# Sheet1.net
KiCad netlist of a schematic drawn in Altium Designer
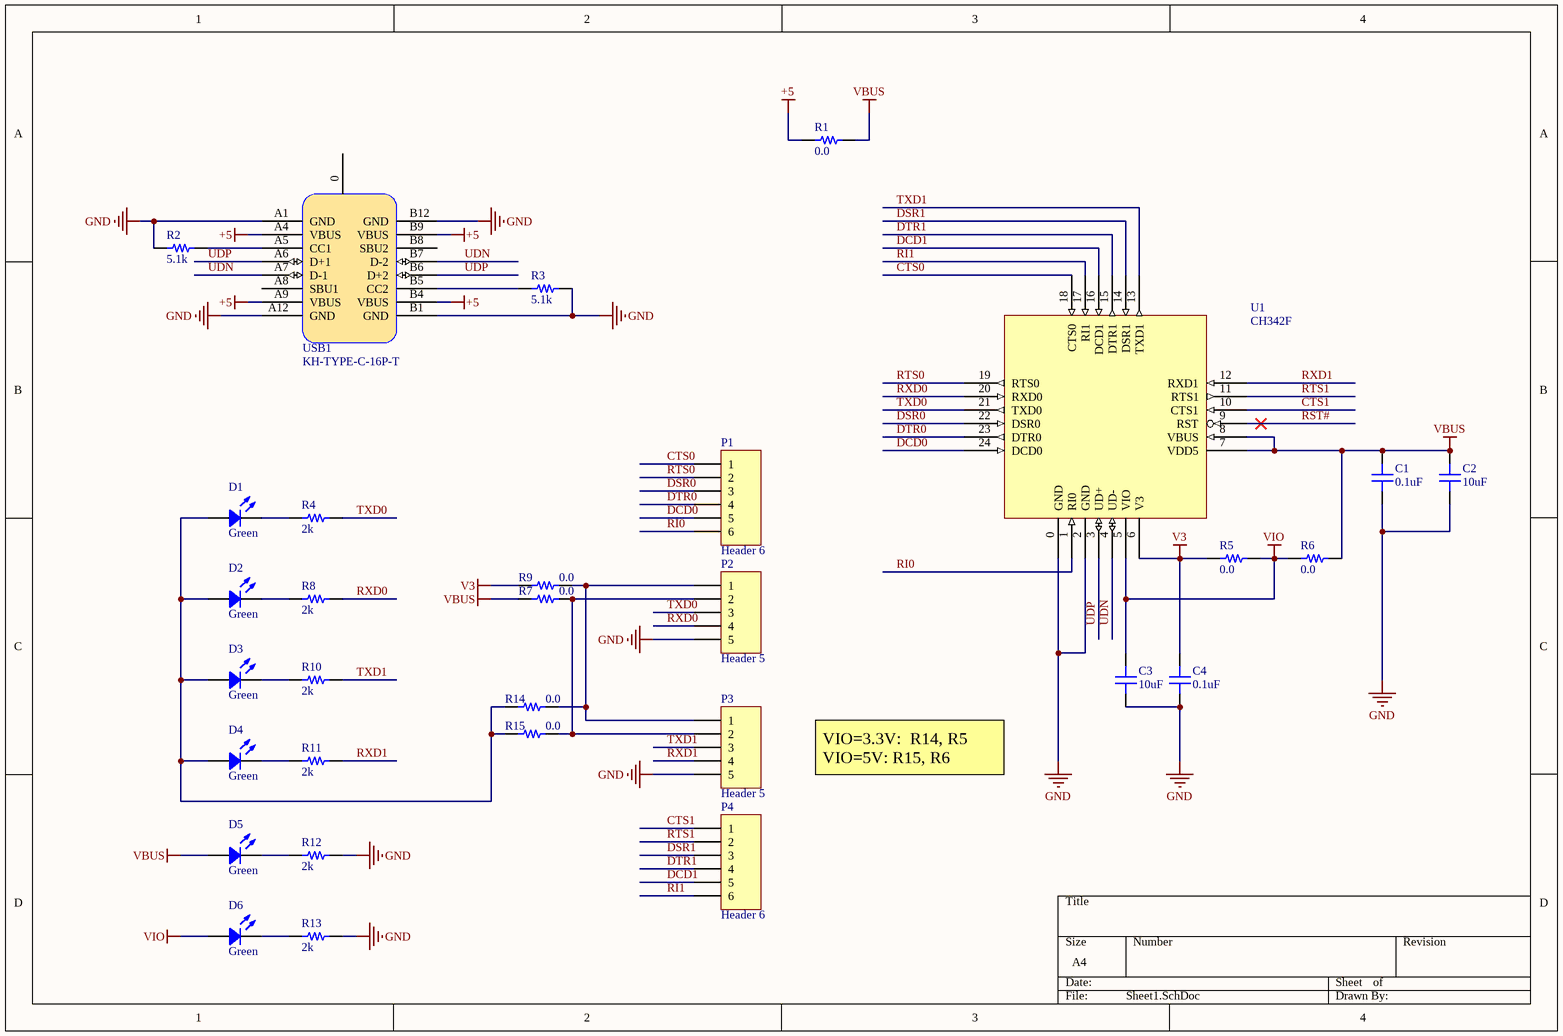
[diagram p0: Sheet1.SchDoc]

(export (version "E")
  (design (tool "Eeschema 10.0.6"))
  (components
    (comp (ref "C1")
      (value "0.1uF")
      (footprint "CAP 0402/1005")
      (description "CAP CER 0.1UF 16V X7R 0402")
      (fields
        (field (name "PART NUMBER") "C1005X7R1C104K050BC")
        (field (name "MANUFACTURER") "TDK Corporation")
      )
      (libsource (lib "Celestial Library Database") (part "Capacitor"))
    )
    (comp (ref "C2")
      (value "10uF")
      (footprint "CAP 0805/2012")
      (description "CAP CER 10UF 10V X5R 0805")
      (fields
        (field (name "PART NUMBER") "C2012X5R1A106K125AB")
        (field (name "MANUFACTURER") "TDK Corporation")
      )
      (libsource (lib "Celestial Library Database") (part "Capacitor"))
    )
    (comp (ref "C3")
      (value "10uF")
      (footprint "CAP 0805/2012")
      (description "CAP CER 10UF 10V X5R 0805")
      (fields
        (field (name "PART NUMBER") "C2012X5R1A106K125AB")
        (field (name "MANUFACTURER") "TDK Corporation")
      )
      (libsource (lib "Celestial Library Database") (part "Capacitor"))
    )
    (comp (ref "C4")
      (value "0.1uF")
      (footprint "CAP 0402/1005")
      (description "CAP CER 0.1UF 16V X7R 0402")
      (fields
        (field (name "PART NUMBER") "C1005X7R1C104K050BC")
        (field (name "MANUFACTURER") "TDK Corporation")
      )
      (libsource (lib "Celestial Library Database") (part "Capacitor"))
    )
    (comp (ref "D1")
      (value "Green")
      (footprint "LED 0805/2012 GREEN")
      (description "LED GREEN CLEAR 0805 SMD")
      (fields (field (name "PART NUMBER") "LTST-C171GKT") (field (name "MANUFACTURER") "Lite-On Inc."))
      (libsource (lib "Celestial Library Database") (part "LED"))
    )
    (comp (ref "D2")
      (value "Green")
      (footprint "LED 0805/2012 GREEN")
      (description "LED GREEN CLEAR 0805 SMD")
      (fields (field (name "PART NUMBER") "LTST-C171GKT") (field (name "MANUFACTURER") "Lite-On Inc."))
      (libsource (lib "Celestial Library Database") (part "LED"))
    )
    (comp (ref "D3")
      (value "Green")
      (footprint "LED 0805/2012 GREEN")
      (description "LED GREEN CLEAR 0805 SMD")
      (fields (field (name "PART NUMBER") "LTST-C171GKT") (field (name "MANUFACTURER") "Lite-On Inc."))
      (libsource (lib "Celestial Library Database") (part "LED"))
    )
    (comp (ref "D4")
      (value "Green")
      (footprint "LED 0805/2012 GREEN")
      (description "LED GREEN CLEAR 0805 SMD")
      (fields (field (name "PART NUMBER") "LTST-C171GKT") (field (name "MANUFACTURER") "Lite-On Inc."))
      (libsource (lib "Celestial Library Database") (part "LED"))
    )
    (comp (ref "D5")
      (value "Green")
      (footprint "LED 0805/2012 GREEN")
      (description "LED GREEN CLEAR 0805 SMD")
      (fields (field (name "PART NUMBER") "LTST-C171GKT") (field (name "MANUFACTURER") "Lite-On Inc."))
      (libsource (lib "Celestial Library Database") (part "LED"))
    )
    (comp (ref "D6")
      (value "Green")
      (footprint "LED 0805/2012 GREEN")
      (description "LED GREEN CLEAR 0805 SMD")
      (fields (field (name "PART NUMBER") "LTST-C171GKT") (field (name "MANUFACTURER") "Lite-On Inc."))
      (libsource (lib "Celestial Library Database") (part "LED"))
    )
    (comp (ref "P1")
      (value "Header 6")
      (footprint "HDR1X6")
      (description "Header, 6-Pin")
      (fields (field (name "PUBLISHER") "Altium Limited"))
      (libsource (lib "Miscellaneous Connectors") (part "Header 6"))
    )
    (comp (ref "P2")
      (value "Header 5")
      (footprint "HDR1X5")
      (description "Header, 5-Pin")
      (fields (field (name "PUBLISHER") "Altium Limited"))
      (libsource (lib "Miscellaneous Connectors") (part "Header 5"))
    )
    (comp (ref "P3")
      (value "Header 5")
      (footprint "HDR1X5")
      (description "Header, 5-Pin")
      (fields (field (name "PUBLISHER") "Altium Limited"))
      (libsource (lib "Miscellaneous Connectors") (part "Header 5"))
    )
    (comp (ref "P4")
      (value "Header 6")
      (footprint "HDR1X6")
      (description "Header, 6-Pin")
      (fields (field (name "PUBLISHER") "Altium Limited"))
      (libsource (lib "Miscellaneous Connectors") (part "Header 6"))
    )
    (comp (ref "R1")
      (value "0.0")
      (footprint "RES 0805/2012")
      (description "RES SMD 0.0 OHM JUMPER 1/8W 0805")
      (fields (field (name "PART NUMBER") "MCR10EZPJ000") (field (name "MANUFACTURER") "Rohm Semiconductor"))
      (libsource (lib "Celestial Library Database") (part "Resistor"))
    )
    (comp (ref "R2")
      (value "5.1k")
      (footprint "RES 0402/1005")
      (description "RES SMD 5.1K OHM 1% 1/10W 0402")
      (fields
        (field (name "PART NUMBER") "ERJ-2RKF5101X")
        (field (name "MANUFACTURER") "Panasonic Electronic Components")
      )
      (libsource (lib "Celestial Library Database") (part "Resistor"))
    )
    (comp (ref "R3")
      (value "5.1k")
      (footprint "RES 0402/1005")
      (description "RES SMD 5.1K OHM 1% 1/10W 0402")
      (fields
        (field (name "PART NUMBER") "ERJ-2RKF5101X")
        (field (name "MANUFACTURER") "Panasonic Electronic Components")
      )
      (libsource (lib "Celestial Library Database") (part "Resistor"))
    )
    (comp (ref "R4")
      (value "2k")
      (footprint "RES 0402/1005")
      (description "RES SMD 2K OHM 5% 1/16W 0402")
      (fields (field (name "PART NUMBER") "RC0402JR-072KL") (field (name "MANUFACTURER") "Yageo"))
      (libsource (lib "Celestial Library Database") (part "Resistor"))
    )
    (comp (ref "R5")
      (value "0.0")
      (footprint "RES 0805/2012")
      (description "RES SMD 0.0 OHM JUMPER 1/8W 0805")
      (fields (field (name "PART NUMBER") "MCR10EZPJ000") (field (name "MANUFACTURER") "Rohm Semiconductor"))
      (libsource (lib "Celestial Library Database") (part "Resistor"))
    )
    (comp (ref "R6")
      (value "0.0")
      (footprint "RES 0805/2012")
      (description "RES SMD 0.0 OHM JUMPER 1/8W 0805")
      (fields (field (name "PART NUMBER") "MCR10EZPJ000") (field (name "MANUFACTURER") "Rohm Semiconductor"))
      (libsource (lib "Celestial Library Database") (part "Resistor"))
    )
    (comp (ref "R7")
      (value "0.0")
      (footprint "RES 0805/2012")
      (description "RES SMD 0.0 OHM JUMPER 1/8W 0805")
      (fields (field (name "PART NUMBER") "MCR10EZPJ000") (field (name "MANUFACTURER") "Rohm Semiconductor"))
      (libsource (lib "Celestial Library Database") (part "Resistor"))
    )
    (comp (ref "R8")
      (value "2k")
      (footprint "RES 0402/1005")
      (description "RES SMD 2K OHM 5% 1/16W 0402")
      (fields (field (name "PART NUMBER") "RC0402JR-072KL") (field (name "MANUFACTURER") "Yageo"))
      (libsource (lib "Celestial Library Database") (part "Resistor"))
    )
    (comp (ref "R9")
      (value "0.0")
      (footprint "RES 0805/2012")
      (description "RES SMD 0.0 OHM JUMPER 1/8W 0805")
      (fields (field (name "PART NUMBER") "MCR10EZPJ000") (field (name "MANUFACTURER") "Rohm Semiconductor"))
      (libsource (lib "Celestial Library Database") (part "Resistor"))
    )
    (comp (ref "R10")
      (value "2k")
      (footprint "RES 0402/1005")
      (description "RES SMD 2K OHM 5% 1/16W 0402")
      (fields (field (name "PART NUMBER") "RC0402JR-072KL") (field (name "MANUFACTURER") "Yageo"))
      (libsource (lib "Celestial Library Database") (part "Resistor"))
    )
    (comp (ref "R11")
      (value "2k")
      (footprint "RES 0402/1005")
      (description "RES SMD 2K OHM 5% 1/16W 0402")
      (fields (field (name "PART NUMBER") "RC0402JR-072KL") (field (name "MANUFACTURER") "Yageo"))
      (libsource (lib "Celestial Library Database") (part "Resistor"))
    )
    (comp (ref "R12")
      (value "2k")
      (footprint "RES 0402/1005")
      (description "RES SMD 2K OHM 5% 1/16W 0402")
      (fields (field (name "PART NUMBER") "RC0402JR-072KL") (field (name "MANUFACTURER") "Yageo"))
      (libsource (lib "Celestial Library Database") (part "Resistor"))
    )
    (comp (ref "R13")
      (value "2k")
      (footprint "RES 0402/1005")
      (description "RES SMD 2K OHM 5% 1/16W 0402")
      (fields (field (name "PART NUMBER") "RC0402JR-072KL") (field (name "MANUFACTURER") "Yageo"))
      (libsource (lib "Celestial Library Database") (part "Resistor"))
    )
    (comp (ref "R14")
      (value "0.0")
      (footprint "RES 0402/1005")
      (description "RES SMD 0.0OHM JUMPER 1/10W 0402")
      (fields
        (field (name "PART NUMBER") "ERJ-2GE0R00X")
        (field (name "MANUFACTURER") "Panasonic Electronic Components")
      )
      (libsource (lib "Celestial Library Database") (part "Resistor"))
    )
    (comp (ref "R15")
      (value "0.0")
      (footprint "RES 0402/1005")
      (description "RES SMD 0.0OHM JUMPER 1/10W 0402")
      (fields
        (field (name "PART NUMBER") "ERJ-2GE0R00X")
        (field (name "MANUFACTURER") "Panasonic Electronic Components")
      )
      (libsource (lib "Celestial Library Database") (part "Resistor"))
    )
    (comp (ref "U1")
      (value "CH342F")
      (footprint "QFN24_4X4")
      (description "USB to dual enhanced TTL Serial / 2*UART")
      (libsource (lib "WCH-CHxxx") (part "CH342F"))
    )
    (comp (ref "USB1")
      (value "KH-TYPE-C-16P-T")
      (footprint "TYPE-C-M-16P")
      (description "Type-C母座 16PIN 立式四角贴板双压片")
      (libsource (lib "USB") (part "KH-TYPE-C-16P-T"))
    )
  )
  (nets
    (net (code "1") (name "+5") (class "Default")
      (node (ref "R1") (pin "1") (pinfunction "1_1") (pintype "passive"))
      (node (ref "USB1") (pin "A4") (pinfunction "VBUS_A4") (pintype "power_in"))
      (node (ref "USB1") (pin "A9") (pinfunction "VBUS_A9") (pintype "power_in"))
      (node (ref "USB1") (pin "B4") (pinfunction "VBUS_B4") (pintype "power_in"))
      (node (ref "USB1") (pin "B9") (pinfunction "VBUS_B9") (pintype "power_in"))
    )
    (net (code "2") (name "/CTS0") (class "Default")
      (node (ref "P1") (pin "1") (pinfunction "1_1") (pintype "passive"))
      (node (ref "U1") (pin "18") (pinfunction "CTS0_18") (pintype "input"))
    )
    (net (code "3") (name "/CTS1") (class "Default")
      (node (ref "P4") (pin "1") (pinfunction "1_1") (pintype "passive"))
      (node (ref "U1") (pin "10") (pinfunction "CTS1_10") (pintype "input"))
    )
    (net (code "4") (name "/DCD0") (class "Default")
      (node (ref "P1") (pin "5") (pinfunction "5_5") (pintype "passive"))
      (node (ref "U1") (pin "24") (pinfunction "DCD0_24") (pintype "input"))
    )
    (net (code "5") (name "/DCD1") (class "Default")
      (node (ref "P4") (pin "5") (pinfunction "5_5") (pintype "passive"))
      (node (ref "U1") (pin "16") (pinfunction "DCD1_16") (pintype "input"))
    )
    (net (code "6") (name "/DSR0") (class "Default")
      (node (ref "P1") (pin "3") (pinfunction "3_3") (pintype "passive"))
      (node (ref "U1") (pin "22") (pinfunction "DSR0_22") (pintype "input"))
    )
    (net (code "7") (name "/DSR1") (class "Default")
      (node (ref "P4") (pin "3") (pinfunction "3_3") (pintype "passive"))
      (node (ref "U1") (pin "14") (pinfunction "DSR1_14") (pintype "input"))
    )
    (net (code "8") (name "/DTR0") (class "Default")
      (node (ref "P1") (pin "4") (pinfunction "4_4") (pintype "passive"))
      (node (ref "U1") (pin "23") (pinfunction "DTR0_23") (pintype "output"))
    )
    (net (code "9") (name "/DTR1") (class "Default")
      (node (ref "P4") (pin "4") (pinfunction "4_4") (pintype "passive"))
      (node (ref "U1") (pin "15") (pinfunction "DTR1_15") (pintype "output"))
    )
    (net (code "10") (name "/RI0") (class "Default")
      (node (ref "P1") (pin "6") (pinfunction "6_6") (pintype "passive"))
      (node (ref "U1") (pin "1") (pinfunction "RI0_1") (pintype "input"))
    )
    (net (code "11") (name "/RI1") (class "Default")
      (node (ref "P4") (pin "6") (pinfunction "6_6") (pintype "passive"))
      (node (ref "U1") (pin "17") (pinfunction "RI1_17") (pintype "input"))
    )
    (net (code "12") (name "/RST#") (class "Default")
      (node (ref "U1") (pin "9") (pinfunction "RST_9") (pintype "input"))
    )
    (net (code "13") (name "/RTS0") (class "Default")
      (node (ref "P1") (pin "2") (pinfunction "2_2") (pintype "passive"))
      (node (ref "U1") (pin "19") (pinfunction "RTS0_19") (pintype "output"))
    )
    (net (code "14") (name "/RTS1") (class "Default")
      (node (ref "P4") (pin "2") (pinfunction "2_2") (pintype "passive"))
      (node (ref "U1") (pin "11") (pinfunction "RTS1_11") (pintype "output"))
    )
    (net (code "15") (name "/RXD0") (class "Default")
      (node (ref "P2") (pin "4") (pinfunction "4_4") (pintype "passive"))
      (node (ref "R8") (pin "1") (pinfunction "1_1") (pintype "passive"))
      (node (ref "U1") (pin "20") (pinfunction "RXD0_20") (pintype "input"))
    )
    (net (code "16") (name "/RXD1") (class "Default")
      (node (ref "P3") (pin "4") (pinfunction "4_4") (pintype "passive"))
      (node (ref "R11") (pin "1") (pinfunction "1_1") (pintype "passive"))
      (node (ref "U1") (pin "12") (pinfunction "RXD1_12") (pintype "input"))
    )
    (net (code "17") (name "/TXD0") (class "Default")
      (node (ref "P2") (pin "3") (pinfunction "3_3") (pintype "passive"))
      (node (ref "R4") (pin "1") (pinfunction "1_1") (pintype "passive"))
      (node (ref "U1") (pin "21") (pinfunction "TXD0_21") (pintype "output"))
    )
    (net (code "18") (name "/TXD1") (class "Default")
      (node (ref "P3") (pin "3") (pinfunction "3_3") (pintype "passive"))
      (node (ref "R10") (pin "1") (pinfunction "1_1") (pintype "passive"))
      (node (ref "U1") (pin "13") (pinfunction "TXD1_13") (pintype "output"))
    )
    (net (code "19") (name "/UDN") (class "Default")
      (node (ref "U1") (pin "4") (pinfunction "UD-_4") (pintype "bidirectional"))
      (node (ref "USB1") (pin "A7") (pinfunction "D-1_A7") (pintype "bidirectional"))
      (node (ref "USB1") (pin "B7") (pinfunction "D-2_B7") (pintype "bidirectional"))
    )
    (net (code "20") (name "/UDP") (class "Default")
      (node (ref "U1") (pin "3") (pinfunction "UD+_3") (pintype "bidirectional"))
      (node (ref "USB1") (pin "A6") (pinfunction "D+1_A6") (pintype "bidirectional"))
      (node (ref "USB1") (pin "B6") (pinfunction "D+2_B6") (pintype "bidirectional"))
    )
    (net (code "21") (name "GND") (class "Default")
      (node (ref "C1") (pin "1") (pinfunction "1_1") (pintype "passive"))
      (node (ref "C2") (pin "1") (pinfunction "1_1") (pintype "passive"))
      (node (ref "C3") (pin "1") (pinfunction "1_1") (pintype "passive"))
      (node (ref "C4") (pin "1") (pinfunction "1_1") (pintype "passive"))
      (node (ref "P2") (pin "5") (pinfunction "5_5") (pintype "passive"))
      (node (ref "P3") (pin "5") (pinfunction "5_5") (pintype "passive"))
      (node (ref "R12") (pin "1") (pinfunction "1_1") (pintype "passive"))
      (node (ref "R13") (pin "1") (pinfunction "1_1") (pintype "passive"))
      (node (ref "R2") (pin "1") (pinfunction "1_1") (pintype "passive"))
      (node (ref "R3") (pin "2") (pinfunction "2_2") (pintype "passive"))
      (node (ref "U1") (pin "0") (pinfunction "GND_0") (pintype "power_in"))
      (node (ref "U1") (pin "2") (pinfunction "GND_2") (pintype "power_in"))
      (node (ref "USB1") (pin "A1") (pinfunction "GND_A1") (pintype "power_in"))
      (node (ref "USB1") (pin "A12") (pinfunction "GND_A12") (pintype "power_in"))
      (node (ref "USB1") (pin "B1") (pinfunction "GND_B1") (pintype "power_in"))
      (node (ref "USB1") (pin "B12") (pinfunction "GND_B12") (pintype "power_in"))
    )
    (net (code "22") (name "Net-(D1-Pad1)") (class "Default")
      (node (ref "D1") (pin "1") (pinfunction "1_1") (pintype "passive"))
      (node (ref "D2") (pin "1") (pinfunction "1_1") (pintype "passive"))
      (node (ref "D3") (pin "1") (pinfunction "1_1") (pintype "passive"))
      (node (ref "D4") (pin "1") (pinfunction "1_1") (pintype "passive"))
      (node (ref "R14") (pin "1") (pinfunction "1_1") (pintype "passive"))
      (node (ref "R15") (pin "1") (pinfunction "1_1") (pintype "passive"))
    )
    (net (code "23") (name "Net-(D1-Pad2)") (class "Default")
      (node (ref "D1") (pin "2") (pinfunction "2_2") (pintype "passive"))
      (node (ref "R4") (pin "2") (pinfunction "2_2") (pintype "passive"))
    )
    (net (code "24") (name "Net-(D2-Pad2)") (class "Default")
      (node (ref "D2") (pin "2") (pinfunction "2_2") (pintype "passive"))
      (node (ref "R8") (pin "2") (pinfunction "2_2") (pintype "passive"))
    )
    (net (code "25") (name "Net-(D3-Pad2)") (class "Default")
      (node (ref "D3") (pin "2") (pinfunction "2_2") (pintype "passive"))
      (node (ref "R10") (pin "2") (pinfunction "2_2") (pintype "passive"))
    )
    (net (code "26") (name "Net-(D4-Pad2)") (class "Default")
      (node (ref "D4") (pin "2") (pinfunction "2_2") (pintype "passive"))
      (node (ref "R11") (pin "2") (pinfunction "2_2") (pintype "passive"))
    )
    (net (code "27") (name "Net-(D5-Pad2)") (class "Default")
      (node (ref "D5") (pin "2") (pinfunction "2_2") (pintype "passive"))
      (node (ref "R12") (pin "2") (pinfunction "2_2") (pintype "passive"))
    )
    (net (code "28") (name "Net-(D6-Pad2)") (class "Default")
      (node (ref "D6") (pin "2") (pinfunction "2_2") (pintype "passive"))
      (node (ref "R13") (pin "2") (pinfunction "2_2") (pintype "passive"))
    )
    (net (code "29") (name "Net-(P2-Pad1)") (class "Default")
      (node (ref "P2") (pin "1") (pinfunction "1_1") (pintype "passive"))
      (node (ref "P3") (pin "1") (pinfunction "1_1") (pintype "passive"))
      (node (ref "R14") (pin "2") (pinfunction "2_2") (pintype "passive"))
      (node (ref "R9") (pin "2") (pinfunction "2_2") (pintype "passive"))
    )
    (net (code "30") (name "Net-(P2-Pad2)") (class "Default")
      (node (ref "P2") (pin "2") (pinfunction "2_2") (pintype "passive"))
      (node (ref "P3") (pin "2") (pinfunction "2_2") (pintype "passive"))
      (node (ref "R15") (pin "2") (pinfunction "2_2") (pintype "passive"))
      (node (ref "R7") (pin "2") (pinfunction "2_2") (pintype "passive"))
    )
    (net (code "31") (name "Net-(USB1-CC1)") (class "Default")
      (node (ref "R2") (pin "2") (pinfunction "2_2") (pintype "passive"))
      (node (ref "USB1") (pin "A5") (pinfunction "CC1_A5") (pintype "passive"))
    )
    (net (code "32") (name "Net-(USB1-CC2)") (class "Default")
      (node (ref "R3") (pin "1") (pinfunction "1_1") (pintype "passive"))
      (node (ref "USB1") (pin "B5") (pinfunction "CC2_B5") (pintype "passive"))
    )
    (net (code "33") (name "V3") (class "Default")
      (node (ref "C4") (pin "2") (pinfunction "2_2") (pintype "passive"))
      (node (ref "R5") (pin "1") (pinfunction "1_1") (pintype "passive"))
      (node (ref "R9") (pin "1") (pinfunction "1_1") (pintype "passive"))
      (node (ref "U1") (pin "6") (pinfunction "V3_6") (pintype "power_in"))
    )
    (net (code "34") (name "VBUS") (class "Default")
      (node (ref "C1") (pin "2") (pinfunction "2_2") (pintype "passive"))
      (node (ref "C2") (pin "2") (pinfunction "2_2") (pintype "passive"))
      (node (ref "D5") (pin "1") (pinfunction "1_1") (pintype "passive"))
      (node (ref "R1") (pin "2") (pinfunction "2_2") (pintype "passive"))
      (node (ref "R6") (pin "2") (pinfunction "2_2") (pintype "passive"))
      (node (ref "R7") (pin "1") (pinfunction "1_1") (pintype "passive"))
      (node (ref "U1") (pin "7") (pinfunction "VDD5_7") (pintype "power_in"))
      (node (ref "U1") (pin "8") (pinfunction "VBUS_8") (pintype "input"))
    )
    (net (code "35") (name "VIO") (class "Default")
      (node (ref "C3") (pin "2") (pinfunction "2_2") (pintype "passive"))
      (node (ref "D6") (pin "1") (pinfunction "1_1") (pintype "passive"))
      (node (ref "R5") (pin "2") (pinfunction "2_2") (pintype "passive"))
      (node (ref "R6") (pin "1") (pinfunction "1_1") (pintype "passive"))
      (node (ref "U1") (pin "5") (pinfunction "VIO_5") (pintype "power_in"))
    )
    (net (code "36") (name "unconnected-(USB1-Pad0)") (class "Default")
      (node (ref "USB1") (pin "0") (pinfunction "0_0") (pintype "passive"))
    )
    (net (code "37") (name "unconnected-(USB1-SBU1-PadA8)") (class "Default")
      (node (ref "USB1") (pin "A8") (pinfunction "SBU1_A8") (pintype "passive"))
    )
    (net (code "38") (name "unconnected-(USB1-SBU2-PadB8)") (class "Default")
      (node (ref "USB1") (pin "B8") (pinfunction "SBU2_B8") (pintype "passive"))
    )
  )
)
